# pmu.net
KiCad netlist of a schematic drawn in EAGLE
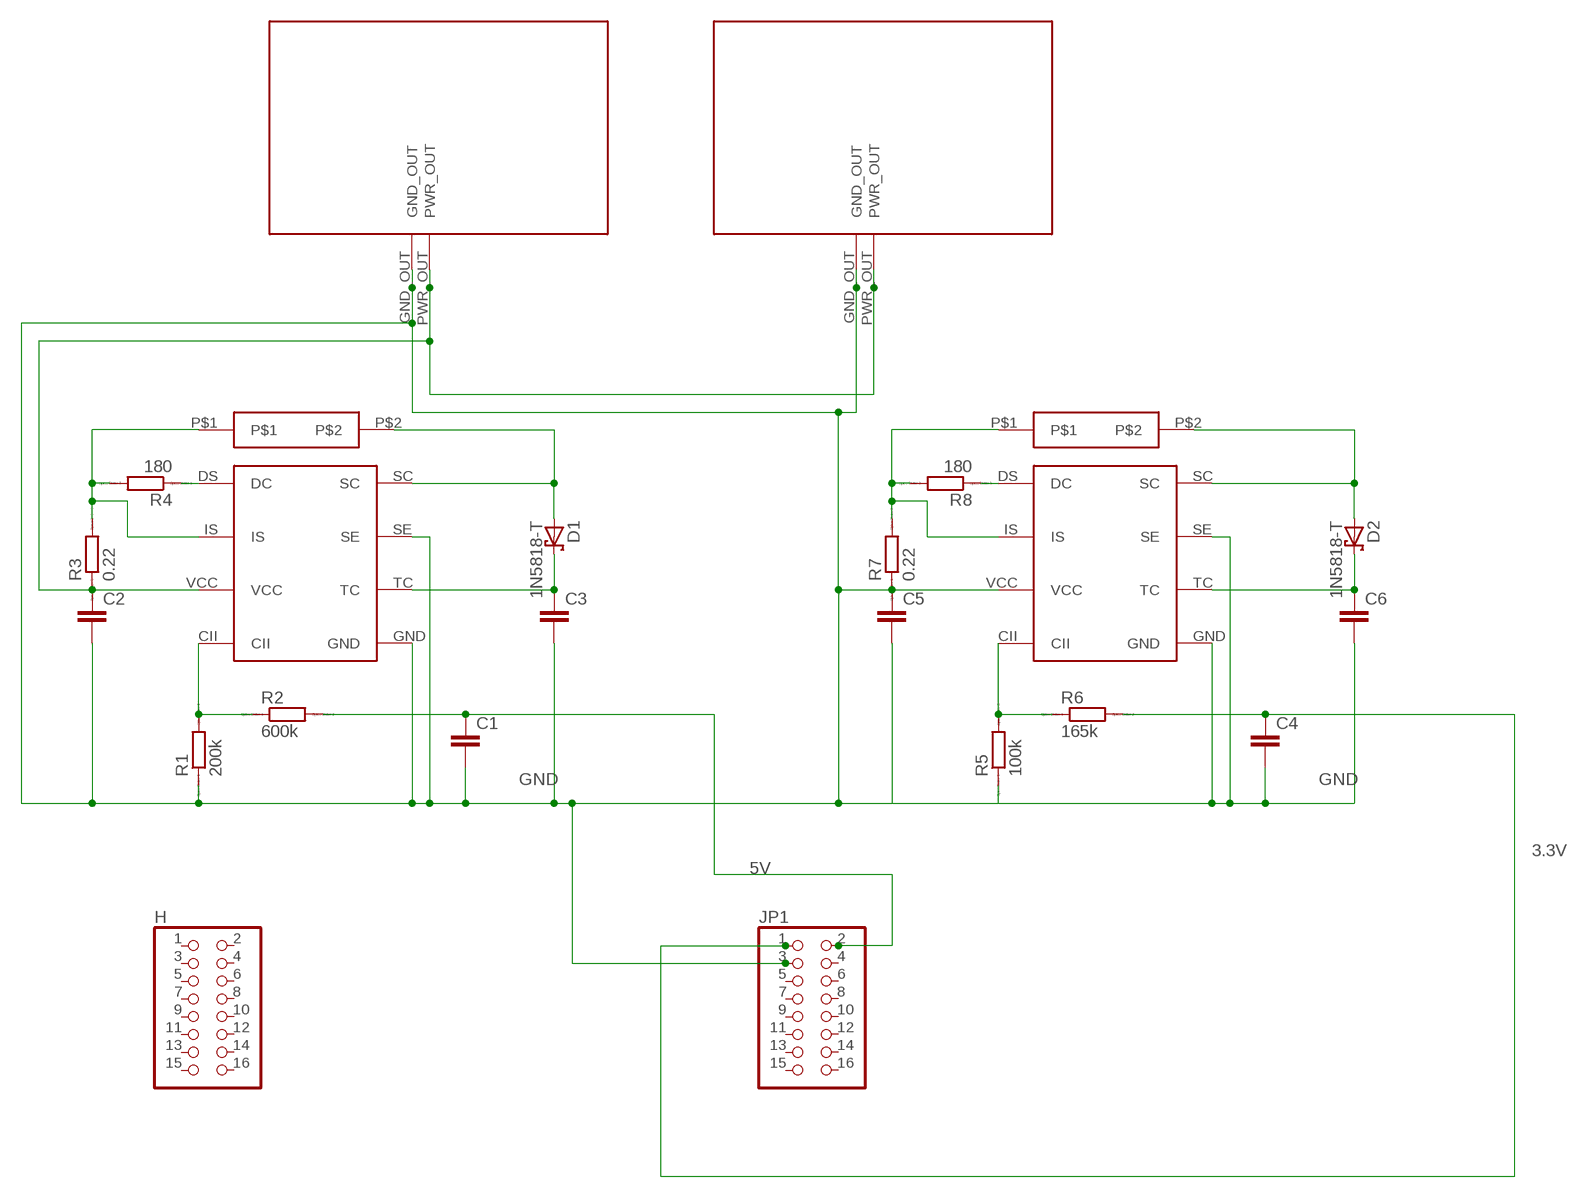
[diagram p0: schematic, sheet 1]

(export (version "E")
  (design (tool "Eeschema 10.0.6"))
  (components
    (comp (ref "C1")
      (value "C2.5/6")
      (footprint "eagle-import:C2.5-6")
      (libsource (lib "eagle-import") (part "C2.5/6"))
    )
    (comp (ref "C2")
      (value "C2.5/6")
      (footprint "eagle-import:C2.5-6")
      (libsource (lib "eagle-import") (part "C2.5/6"))
    )
    (comp (ref "C3")
      (value "C2.5/6")
      (footprint "eagle-import:C2.5-6")
      (libsource (lib "eagle-import") (part "C2.5/6"))
    )
    (comp (ref "C4")
      (value "C2.5/6")
      (footprint "eagle-import:C2.5-6")
      (libsource (lib "eagle-import") (part "C2.5/6"))
    )
    (comp (ref "C5")
      (value "C2.5/6")
      (footprint "eagle-import:C2.5-6")
      (libsource (lib "eagle-import") (part "C2.5/6"))
    )
    (comp (ref "C6")
      (value "C2.5/6")
      (footprint "eagle-import:C2.5-6")
      (libsource (lib "eagle-import") (part "C2.5/6"))
    )
    (comp (ref "D1")
      (value "1N5818-T")
      (footprint "eagle-import:DO41-7.6")
      (libsource (lib "eagle-import") (part "1N5818-T"))
    )
    (comp (ref "D2")
      (value "1N5818-T")
      (footprint "eagle-import:DO41-7.6")
      (libsource (lib "eagle-import") (part "1N5818-T"))
    )
    (comp (ref "H")
      (value "PINHD-2X8")
      (footprint "eagle-import:2X08")
      (libsource (lib "eagle-import") (part "PINHD-2X8"))
    )
    (comp (ref "JP1")
      (value "PINHD-2X8")
      (footprint "eagle-import:2X08")
      (libsource (lib "eagle-import") (part "PINHD-2X8"))
    )
    (comp (ref "R1")
      (value "200k")
      (footprint "eagle-import:0207_12")
      (libsource (lib "eagle-import") (part "R-EU_0207_12"))
    )
    (comp (ref "R2")
      (value "600k")
      (footprint "eagle-import:0207_12")
      (libsource (lib "eagle-import") (part "R-EU_0207_12"))
    )
    (comp (ref "R3")
      (value "0.22")
      (footprint "eagle-import:0207_12")
      (libsource (lib "eagle-import") (part "R-EU_0207_12"))
    )
    (comp (ref "R4")
      (value "180")
      (footprint "eagle-import:0207_12")
      (libsource (lib "eagle-import") (part "R-EU_0207_12"))
    )
    (comp (ref "R5")
      (value "100k")
      (footprint "eagle-import:0207_12")
      (libsource (lib "eagle-import") (part "R-EU_0207_12"))
    )
    (comp (ref "R6")
      (value "165k")
      (footprint "eagle-import:0207_12")
      (libsource (lib "eagle-import") (part "R-EU_0207_12"))
    )
    (comp (ref "R7")
      (value "0.22")
      (footprint "eagle-import:0207_12")
      (libsource (lib "eagle-import") (part "R-EU_0207_12"))
    )
    (comp (ref "R8")
      (value "180")
      (footprint "eagle-import:0207_12")
      (libsource (lib "eagle-import") (part "R-EU_0207_12"))
    )
    (comp (ref "U$1")
      (value "CHAR")
      (footprint "eagle-import:CHAR")
      (libsource (lib "eagle-import") (part "CHAR"))
    )
    (comp (ref "U$2")
      (value "CHAR")
      (footprint "eagle-import:CHAR")
      (libsource (lib "eagle-import") (part "CHAR"))
    )
    (comp (ref "U$3")
      (value "TIBB")
      (footprint "eagle-import:TIBB")
      (libsource (lib "eagle-import") (part "TIBB"))
    )
    (comp (ref "U$4")
      (value "IND")
      (footprint "eagle-import:8RHT2")
      (libsource (lib "eagle-import") (part "IND"))
    )
    (comp (ref "U$5")
      (value "TIBB")
      (footprint "eagle-import:TIBB")
      (libsource (lib "eagle-import") (part "TIBB"))
    )
    (comp (ref "U$6")
      (value "IND")
      (footprint "eagle-import:8RHT2")
      (libsource (lib "eagle-import") (part "IND"))
    )
  )
  (nets
    (net (code "1") (name "/3.3V") (class "Default")
      (node (ref "C4") (pin "1") (pinfunction "1_1") (pintype "passive"))
      (node (ref "JP1") (pin "1") (pinfunction "1_1") (pintype "passive"))
      (node (ref "R6") (pin "2") (pinfunction "2_2") (pintype "passive"))
    )
    (net (code "2") (name "/5V") (class "Default")
      (node (ref "C1") (pin "1") (pinfunction "1_1") (pintype "passive"))
      (node (ref "JP1") (pin "2") (pinfunction "2_2") (pintype "passive"))
      (node (ref "R2") (pin "2") (pinfunction "2_2") (pintype "passive"))
    )
    (net (code "3") (name "/GND") (class "Default")
      (node (ref "C1") (pin "2") (pinfunction "2_2") (pintype "passive"))
      (node (ref "C2") (pin "2") (pinfunction "2_2") (pintype "passive"))
      (node (ref "C3") (pin "2") (pinfunction "2_2") (pintype "passive"))
      (node (ref "C4") (pin "2") (pinfunction "2_2") (pintype "passive"))
      (node (ref "C5") (pin "1") (pinfunction "1_1") (pintype "passive"))
      (node (ref "C5") (pin "2") (pinfunction "2_2") (pintype "passive"))
      (node (ref "C6") (pin "2") (pinfunction "2_2") (pintype "passive"))
      (node (ref "JP1") (pin "3") (pinfunction "3_3") (pintype "passive"))
      (node (ref "R1") (pin "1") (pinfunction "1_1") (pintype "passive"))
      (node (ref "R5") (pin "1") (pinfunction "1_1") (pintype "passive"))
      (node (ref "R7") (pin "1") (pinfunction "1_1") (pintype "passive"))
      (node (ref "U$1") (pin "GND_OUT") (pinfunction "GND_OUT_GND_OUT") (pintype "bidirectional"))
      (node (ref "U$2") (pin "GND_OUT") (pinfunction "GND_OUT_GND_OUT") (pintype "bidirectional"))
      (node (ref "U$3") (pin "GND") (pinfunction "GND_GND") (pintype "bidirectional"))
      (node (ref "U$3") (pin "SE") (pinfunction "SE_SE") (pintype "bidirectional"))
      (node (ref "U$5") (pin "GND") (pinfunction "GND_GND") (pintype "bidirectional"))
      (node (ref "U$5") (pin "SE") (pinfunction "SE_SE") (pintype "bidirectional"))
      (node (ref "U$5") (pin "VCC") (pinfunction "VCC_VCC") (pintype "bidirectional"))
    )
    (net (code "4") (name "Net-(C2-Pad1)") (class "Default")
      (node (ref "C2") (pin "1") (pinfunction "1_1") (pintype "passive"))
      (node (ref "R3") (pin "1") (pinfunction "1_1") (pintype "passive"))
      (node (ref "U$1") (pin "PWR_OUT") (pinfunction "PWR_OUT_PWR_OUT") (pintype "bidirectional"))
      (node (ref "U$2") (pin "PWR_OUT") (pinfunction "PWR_OUT_PWR_OUT") (pintype "bidirectional"))
      (node (ref "U$3") (pin "VCC") (pinfunction "VCC_VCC") (pintype "bidirectional"))
    )
    (net (code "5") (name "Net-(C3-Pad1)") (class "Default")
      (node (ref "C3") (pin "1") (pinfunction "1_1") (pintype "passive"))
      (node (ref "D1") (pin "C") (pinfunction "C_C") (pintype "passive"))
      (node (ref "U$3") (pin "TC") (pinfunction "TC_TC") (pintype "bidirectional"))
    )
    (net (code "6") (name "Net-(C6-Pad1)") (class "Default")
      (node (ref "C6") (pin "1") (pinfunction "1_1") (pintype "passive"))
      (node (ref "D2") (pin "C") (pinfunction "C_C") (pintype "passive"))
      (node (ref "U$5") (pin "TC") (pinfunction "TC_TC") (pintype "bidirectional"))
    )
    (net (code "7") (name "Net-(D1-PadA)") (class "Default")
      (node (ref "D1") (pin "A") (pinfunction "A_A") (pintype "passive"))
      (node (ref "U$3") (pin "SC") (pinfunction "SC_SC") (pintype "bidirectional"))
      (node (ref "U$4") (pin "P$2") (pinfunction "P$2_P$2") (pintype "bidirectional"))
    )
    (net (code "8") (name "Net-(D2-PadA)") (class "Default")
      (node (ref "D2") (pin "A") (pinfunction "A_A") (pintype "passive"))
      (node (ref "U$5") (pin "SC") (pinfunction "SC_SC") (pintype "bidirectional"))
      (node (ref "U$6") (pin "P$2") (pinfunction "P$2_P$2") (pintype "bidirectional"))
    )
    (net (code "9") (name "Net-(R1-Pad2)") (class "Default")
      (node (ref "R1") (pin "2") (pinfunction "2_2") (pintype "passive"))
      (node (ref "R2") (pin "1") (pinfunction "1_1") (pintype "passive"))
      (node (ref "U$3") (pin "CII") (pinfunction "CII_CII") (pintype "bidirectional"))
    )
    (net (code "10") (name "Net-(R3-Pad2)") (class "Default")
      (node (ref "R3") (pin "2") (pinfunction "2_2") (pintype "passive"))
      (node (ref "R4") (pin "2") (pinfunction "2_2") (pintype "passive"))
      (node (ref "U$3") (pin "IS") (pinfunction "IS_IS") (pintype "bidirectional"))
      (node (ref "U$4") (pin "P$1") (pinfunction "P$1_P$1") (pintype "bidirectional"))
    )
    (net (code "11") (name "Net-(R5-Pad2)") (class "Default")
      (node (ref "R5") (pin "2") (pinfunction "2_2") (pintype "passive"))
      (node (ref "R6") (pin "1") (pinfunction "1_1") (pintype "passive"))
      (node (ref "U$5") (pin "CII") (pinfunction "CII_CII") (pintype "bidirectional"))
    )
    (net (code "12") (name "Net-(R7-Pad2)") (class "Default")
      (node (ref "R7") (pin "2") (pinfunction "2_2") (pintype "passive"))
      (node (ref "R8") (pin "2") (pinfunction "2_2") (pintype "passive"))
      (node (ref "U$5") (pin "IS") (pinfunction "IS_IS") (pintype "bidirectional"))
      (node (ref "U$6") (pin "P$1") (pinfunction "P$1_P$1") (pintype "bidirectional"))
    )
    (net (code "13") (name "Net-(U$3-DC)") (class "Default")
      (node (ref "R4") (pin "1") (pinfunction "1_1") (pintype "passive"))
      (node (ref "U$3") (pin "DS") (pinfunction "DC_DS") (pintype "bidirectional"))
    )
    (net (code "14") (name "Net-(U$5-DC)") (class "Default")
      (node (ref "R8") (pin "1") (pinfunction "1_1") (pintype "passive"))
      (node (ref "U$5") (pin "DS") (pinfunction "DC_DS") (pintype "bidirectional"))
    )
    (net (code "15") (name "unconnected-(H-Pad1)") (class "Default")
      (node (ref "H") (pin "1") (pinfunction "1_1") (pintype "passive"))
    )
    (net (code "16") (name "unconnected-(H-Pad2)") (class "Default")
      (node (ref "H") (pin "2") (pinfunction "2_2") (pintype "passive"))
    )
    (net (code "17") (name "unconnected-(H-Pad3)") (class "Default")
      (node (ref "H") (pin "3") (pinfunction "3_3") (pintype "passive"))
    )
    (net (code "18") (name "unconnected-(H-Pad4)") (class "Default")
      (node (ref "H") (pin "4") (pinfunction "4_4") (pintype "passive"))
    )
    (net (code "19") (name "unconnected-(H-Pad5)") (class "Default")
      (node (ref "H") (pin "5") (pinfunction "5_5") (pintype "passive"))
    )
    (net (code "20") (name "unconnected-(H-Pad6)") (class "Default")
      (node (ref "H") (pin "6") (pinfunction "6_6") (pintype "passive"))
    )
    (net (code "21") (name "unconnected-(H-Pad7)") (class "Default")
      (node (ref "H") (pin "7") (pinfunction "7_7") (pintype "passive"))
    )
    (net (code "22") (name "unconnected-(H-Pad8)") (class "Default")
      (node (ref "H") (pin "8") (pinfunction "8_8") (pintype "passive"))
    )
    (net (code "23") (name "unconnected-(H-Pad9)") (class "Default")
      (node (ref "H") (pin "9") (pinfunction "9_9") (pintype "passive"))
    )
    (net (code "24") (name "unconnected-(H-Pad10)") (class "Default")
      (node (ref "H") (pin "10") (pinfunction "10_10") (pintype "passive"))
    )
    (net (code "25") (name "unconnected-(H-Pad11)") (class "Default")
      (node (ref "H") (pin "11") (pinfunction "11_11") (pintype "passive"))
    )
    (net (code "26") (name "unconnected-(H-Pad12)") (class "Default")
      (node (ref "H") (pin "12") (pinfunction "12_12") (pintype "passive"))
    )
    (net (code "27") (name "unconnected-(H-Pad13)") (class "Default")
      (node (ref "H") (pin "13") (pinfunction "13_13") (pintype "passive"))
    )
    (net (code "28") (name "unconnected-(H-Pad14)") (class "Default")
      (node (ref "H") (pin "14") (pinfunction "14_14") (pintype "passive"))
    )
    (net (code "29") (name "unconnected-(H-Pad15)") (class "Default")
      (node (ref "H") (pin "15") (pinfunction "15_15") (pintype "passive"))
    )
    (net (code "30") (name "unconnected-(H-Pad16)") (class "Default")
      (node (ref "H") (pin "16") (pinfunction "16_16") (pintype "passive"))
    )
    (net (code "31") (name "unconnected-(JP1-Pad4)") (class "Default")
      (node (ref "JP1") (pin "4") (pinfunction "4_4") (pintype "passive"))
    )
    (net (code "32") (name "unconnected-(JP1-Pad5)") (class "Default")
      (node (ref "JP1") (pin "5") (pinfunction "5_5") (pintype "passive"))
    )
    (net (code "33") (name "unconnected-(JP1-Pad6)") (class "Default")
      (node (ref "JP1") (pin "6") (pinfunction "6_6") (pintype "passive"))
    )
    (net (code "34") (name "unconnected-(JP1-Pad7)") (class "Default")
      (node (ref "JP1") (pin "7") (pinfunction "7_7") (pintype "passive"))
    )
    (net (code "35") (name "unconnected-(JP1-Pad8)") (class "Default")
      (node (ref "JP1") (pin "8") (pinfunction "8_8") (pintype "passive"))
    )
    (net (code "36") (name "unconnected-(JP1-Pad9)") (class "Default")
      (node (ref "JP1") (pin "9") (pinfunction "9_9") (pintype "passive"))
    )
    (net (code "37") (name "unconnected-(JP1-Pad10)") (class "Default")
      (node (ref "JP1") (pin "10") (pinfunction "10_10") (pintype "passive"))
    )
    (net (code "38") (name "unconnected-(JP1-Pad11)") (class "Default")
      (node (ref "JP1") (pin "11") (pinfunction "11_11") (pintype "passive"))
    )
    (net (code "39") (name "unconnected-(JP1-Pad12)") (class "Default")
      (node (ref "JP1") (pin "12") (pinfunction "12_12") (pintype "passive"))
    )
    (net (code "40") (name "unconnected-(JP1-Pad13)") (class "Default")
      (node (ref "JP1") (pin "13") (pinfunction "13_13") (pintype "passive"))
    )
    (net (code "41") (name "unconnected-(JP1-Pad14)") (class "Default")
      (node (ref "JP1") (pin "14") (pinfunction "14_14") (pintype "passive"))
    )
    (net (code "42") (name "unconnected-(JP1-Pad15)") (class "Default")
      (node (ref "JP1") (pin "15") (pinfunction "15_15") (pintype "passive"))
    )
    (net (code "43") (name "unconnected-(JP1-Pad16)") (class "Default")
      (node (ref "JP1") (pin "16") (pinfunction "16_16") (pintype "passive"))
    )
  )
)
